# Kalibracija3.net
KiCad netlist of a schematic drawn in Altium Designer
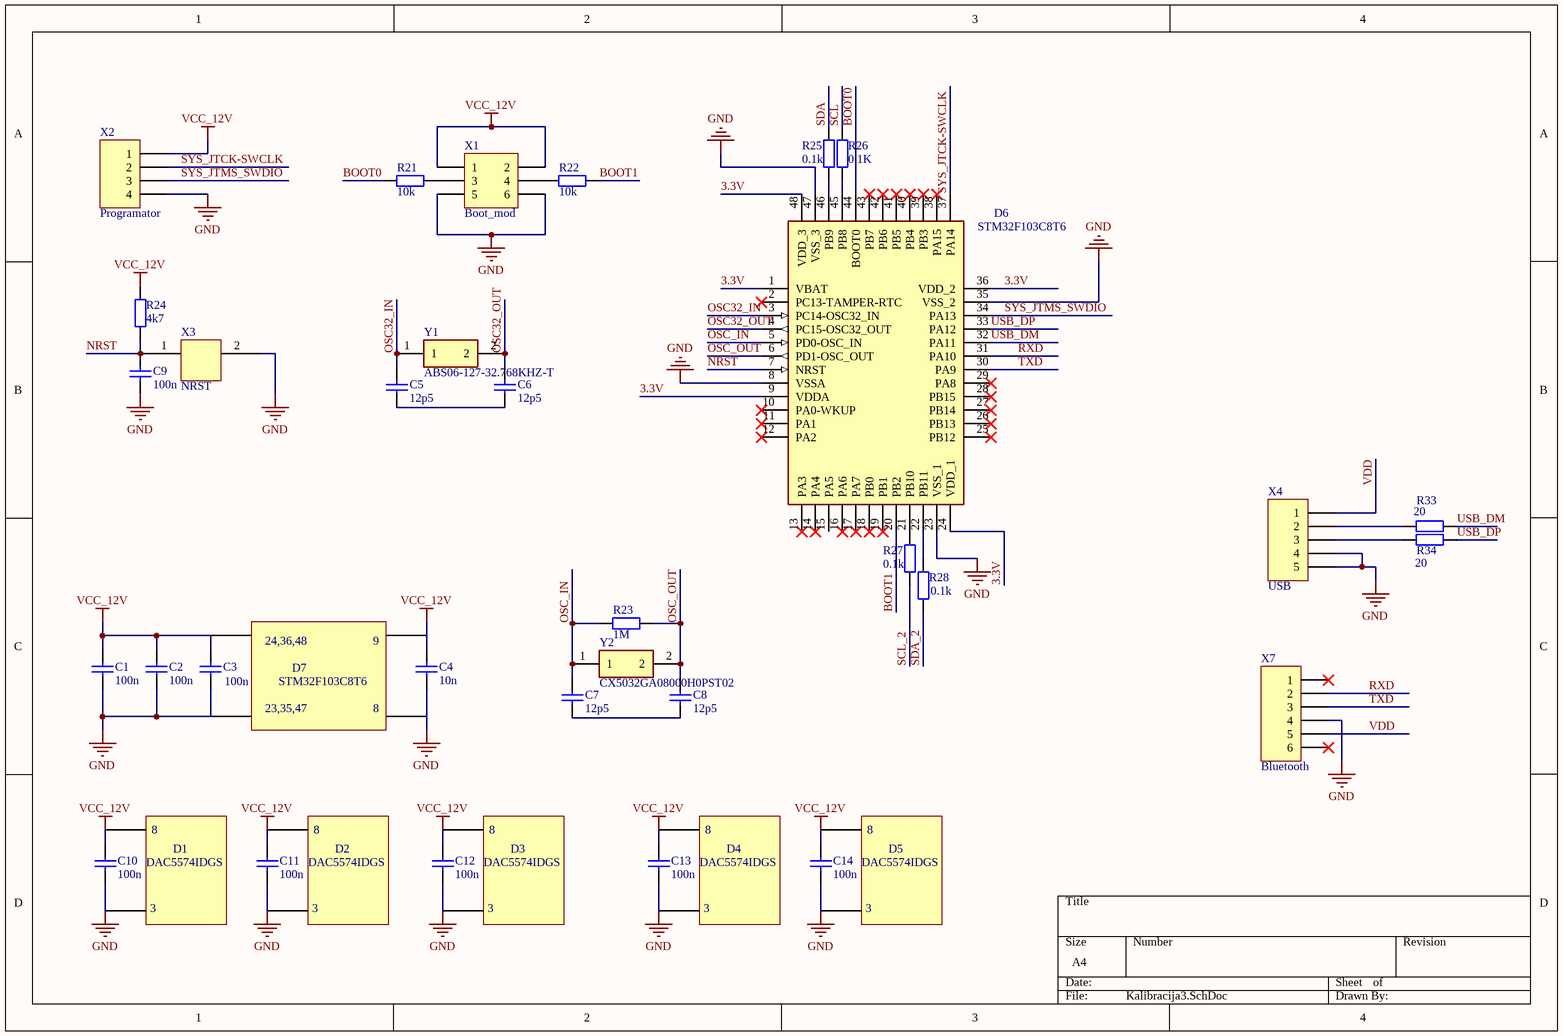
[diagram p0: Kalibracija3.SchDoc]

(export (version "E")
  (design (tool "Eeschema 10.0.6"))
  (components
    (comp (ref "C1")
      (value "100n")
      (footprint "6-0805_N")
      (description "Capacitor")
      (fields (field (name "PUBLISHER") "Altium Limited"))
      (libsource (lib "Miscellaneous Devices") (part "Cap"))
    )
    (comp (ref "C2")
      (value "100n")
      (footprint "6-0805_N")
      (description "Capacitor")
      (fields (field (name "PUBLISHER") "Altium Limited"))
      (libsource (lib "Miscellaneous Devices") (part "Cap"))
    )
    (comp (ref "C3")
      (value "100n")
      (footprint "6-0805_N")
      (description "Capacitor")
      (fields (field (name "PUBLISHER") "Altium Limited"))
      (libsource (lib "Miscellaneous Devices") (part "Cap"))
    )
    (comp (ref "C4")
      (value "10n")
      (footprint "6-0805_N")
      (description "Capacitor")
      (fields (field (name "PUBLISHER") "Altium Limited"))
      (libsource (lib "Miscellaneous Devices") (part "Cap"))
    )
    (comp (ref "C5")
      (value "12p5")
      (footprint "6-0805_N")
      (description "Capacitor")
      (fields (field (name "PUBLISHER") "Altium Limited"))
      (libsource (lib "Miscellaneous Devices") (part "Cap"))
    )
    (comp (ref "C6")
      (value "12p5")
      (footprint "6-0805_N")
      (description "Capacitor")
      (fields (field (name "PUBLISHER") "Altium Limited"))
      (libsource (lib "Miscellaneous Devices") (part "Cap"))
    )
    (comp (ref "C7")
      (value "12p5")
      (footprint "6-0805_N")
      (description "Capacitor")
      (fields (field (name "PUBLISHER") "Altium Limited"))
      (libsource (lib "Miscellaneous Devices") (part "Cap"))
    )
    (comp (ref "C8")
      (value "12p5")
      (footprint "6-0805_N")
      (description "Capacitor")
      (fields (field (name "PUBLISHER") "Altium Limited"))
      (libsource (lib "Miscellaneous Devices") (part "Cap"))
    )
    (comp (ref "C9")
      (value "100n")
      (footprint "6-0805_N")
      (description "Capacitor")
      (fields (field (name "PUBLISHER") "Altium Limited"))
      (libsource (lib "Miscellaneous Devices") (part "Cap"))
    )
    (comp (ref "C10")
      (value "100n")
      (footprint "6-0805_N")
      (description "Capacitor")
      (fields (field (name "PUBLISHER") "Altium Limited"))
      (libsource (lib "Miscellaneous Devices") (part "Cap"))
    )
    (comp (ref "C11")
      (value "100n")
      (footprint "6-0805_N")
      (description "Capacitor")
      (fields (field (name "PUBLISHER") "Altium Limited"))
      (libsource (lib "Miscellaneous Devices") (part "Cap"))
    )
    (comp (ref "C12")
      (value "100n")
      (footprint "6-0805_N")
      (description "Capacitor")
      (fields (field (name "PUBLISHER") "Altium Limited"))
      (libsource (lib "Miscellaneous Devices") (part "Cap"))
    )
    (comp (ref "C13")
      (value "100n")
      (footprint "6-0805_N")
      (description "Capacitor")
      (fields (field (name "PUBLISHER") "Altium Limited"))
      (libsource (lib "Miscellaneous Devices") (part "Cap"))
    )
    (comp (ref "C14")
      (value "100n")
      (footprint "6-0805_N")
      (description "Capacitor")
      (fields (field (name "PUBLISHER") "Altium Limited"))
      (libsource (lib "Miscellaneous Devices") (part "Cap"))
    )
    (comp (ref "D6")
      (value "STM32F103C8T6")
      (footprint "SamacSys:QFP50P900X900X160-48N")
      (description "Integrated Circuit")
      (fields
        (field (name "MOUSER PART NUMBER") "511-STM32F103C8T6")
        (field (name "RS PART NUMBER") "0402279P")
      )
      (libsource (lib "*") (part "STM32F103C8T6"))
    )
    (comp (ref "R21")
      (value "10k")
      (footprint "6-0805_N")
      (description "Resistor")
      (fields (field (name "PUBLISHER") "Altium Limited"))
      (libsource (lib "Miscellaneous Devices") (part "Res2"))
    )
    (comp (ref "R22")
      (value "10k")
      (footprint "6-0805_N")
      (description "Resistor")
      (fields (field (name "PUBLISHER") "Altium Limited"))
      (libsource (lib "Miscellaneous Devices") (part "Res2"))
    )
    (comp (ref "R23")
      (value "1M")
      (footprint "6-0805_N")
      (description "Resistor")
      (fields (field (name "PUBLISHER") "Altium Limited"))
      (libsource (lib "") (part "Res2_1"))
    )
    (comp (ref "R24")
      (value "4k7")
      (footprint "6-0805_N")
      (description "Resistor")
      (fields (field (name "PUBLISHER") "Altium Limited"))
      (libsource (lib "") (part "Res2_3"))
    )
    (comp (ref "R25")
      (value "0.1k")
      (footprint "6-0805_N")
      (description "Resistor")
      (fields (field (name "PUBLISHER") "Altium Limited"))
      (libsource (lib "") (part "Res2_2"))
    )
    (comp (ref "R26")
      (value "0.1K")
      (footprint "6-0805_N")
      (description "Resistor")
      (fields (field (name "PUBLISHER") "Altium Limited"))
      (libsource (lib "") (part "Res2_2"))
    )
    (comp (ref "R27")
      (value "0.1k")
      (footprint "6-0805_N")
      (description "Resistor")
      (fields (field (name "PUBLISHER") "Altium Limited"))
      (libsource (lib "") (part "Res2_2"))
    )
    (comp (ref "R28")
      (value "0.1k")
      (footprint "AXIAL-0.4")
      (description "Resistor")
      (fields (field (name "Comment") "Res2") (field (name "PUBLISHER") "Altium Limited"))
      (libsource (lib "") (part "Res2_2"))
    )
    (comp (ref "R33")
      (value "20")
      (footprint "6-0805_N")
      (description "Resistor")
      (fields (field (name "PUBLISHER") "Altium Limited"))
      (libsource (lib "") (part "Res2_1"))
    )
    (comp (ref "R34")
      (value "20")
      (footprint "6-0805_N")
      (description "Resistor")
      (fields (field (name "PUBLISHER") "Altium Limited"))
      (libsource (lib "") (part "Res2_1"))
    )
    (comp (ref "X1")
      (value "Boot_mod")
      (footprint "HDR2X3")
      (description "Header, 3-Pin, Dual row")
      (fields (field (name "PUBLISHER") "Altium Limited"))
      (libsource (lib "Miscellaneous Connectors") (part "Header 3X2"))
    )
    (comp (ref "X2")
      (value "Programator")
      (footprint "HDR1X4")
      (description "Header, 4-Pin")
      (fields (field (name "PUBLISHER") "Altium Limited"))
      (libsource (lib "Miscellaneous Connectors") (part "Header 4"))
    )
    (comp (ref "X3")
      (value "NRST")
      (footprint "HDR1X2")
      (libsource (lib "altium-import") (part "root_1_jumper_"))
    )
    (comp (ref "X4")
      (value "USB")
      (footprint "HDR1X5")
      (description "Header, 5-Pin")
      (fields (field (name "PUBLISHER") "Altium Limited"))
      (libsource (lib "Miscellaneous Connectors") (part "Header 5"))
    )
    (comp (ref "X7")
      (value "Bluetooth")
      (footprint "HDR1X6")
      (description "Header, 6-Pin")
      (fields (field (name "PUBLISHER") "Altium Limited"))
      (libsource (lib "Miscellaneous Connectors") (part "Header 6"))
    )
    (comp (ref "Y1")
      (value "ABS06-127-32.768KHZ-T")
      (footprint "SamacSys:ABS0612732768KHZT")
      (description "Crystal or Oscillator")
      (fields
        (field (name "MOUSER PART NUMBER") "815-ABS0612732.768KT")
        (field (name "RS PART NUMBER") "1753472P")
      )
      (libsource (lib "*") (part "ABS06-127-32.768KHZ-T"))
    )
    (comp (ref "Y2")
      (value "CX5032GA08000H0PST02")
      (footprint "SamacSys:CX5032GA08000H0PST02")
      (description "Crystal or Oscillator")
      (fields (field (name "MOUSER PART NUMBER") "581-CX5032GA08H0PST"))
      (libsource (lib "*") (part "CX5032GA08000H0PST02"))
    )
  )
  (nets
    (net (code "1") (name "/3.3V") (class "Default")
      (node (ref "D6") (pin "1") (pinfunction "VBAT_1") (pintype "passive"))
      (node (ref "D6") (pin "24") (pinfunction "VDD_1_24") (pintype "power_in"))
      (node (ref "D6") (pin "36") (pinfunction "VDD_2_36") (pintype "power_in"))
      (node (ref "D6") (pin "48") (pinfunction "VDD_3_48") (pintype "power_in"))
      (node (ref "D6") (pin "9") (pinfunction "VDDA_9") (pintype "power_in"))
    )
    (net (code "2") (name "/BOOT0") (class "Default")
      (node (ref "D6") (pin "44") (pinfunction "BOOT0_44") (pintype "passive"))
      (node (ref "R21") (pin "2") (pinfunction "2_2") (pintype "passive"))
    )
    (net (code "3") (name "/BOOT1") (class "Default")
      (node (ref "D6") (pin "20") (pinfunction "PB2_20") (pintype "passive"))
      (node (ref "R22") (pin "1") (pinfunction "1_1") (pintype "passive"))
    )
    (net (code "4") (name "/NRST") (class "Default")
      (node (ref "C9") (pin "2") (pinfunction "2_2") (pintype "passive"))
      (node (ref "D6") (pin "7") (pinfunction "NRST_7") (pintype "input"))
      (node (ref "R24") (pin "2") (pinfunction "2_2") (pintype "passive"))
      (node (ref "X3") (pin "1") (pintype "passive"))
    )
    (net (code "5") (name "/OSC32_IN") (class "Default")
      (node (ref "C5") (pin "2") (pinfunction "2_2") (pintype "passive"))
      (node (ref "D6") (pin "3") (pinfunction "PC14-OSC32_IN_3") (pintype "input"))
      (node (ref "Y1") (pin "1") (pinfunction "1_1") (pintype "passive"))
    )
    (net (code "6") (name "/OSC32_OUT") (class "Default")
      (node (ref "C6") (pin "2") (pinfunction "2_2") (pintype "passive"))
      (node (ref "D6") (pin "4") (pinfunction "PC15-OSC32_OUT_4") (pintype "output"))
      (node (ref "Y1") (pin "2") (pinfunction "2_2") (pintype "passive"))
    )
    (net (code "7") (name "/OSC_IN") (class "Default")
      (node (ref "C7") (pin "2") (pinfunction "2_2") (pintype "passive"))
      (node (ref "D6") (pin "5") (pinfunction "PD0-OSC_IN_5") (pintype "input"))
      (node (ref "R23") (pin "1") (pinfunction "1_1") (pintype "passive"))
      (node (ref "Y2") (pin "1") (pinfunction "1_1") (pintype "passive"))
    )
    (net (code "8") (name "/OSC_OUT") (class "Default")
      (node (ref "C8") (pin "2") (pinfunction "2_2") (pintype "passive"))
      (node (ref "D6") (pin "6") (pinfunction "PD1-OSC_OUT_6") (pintype "output"))
      (node (ref "R23") (pin "2") (pinfunction "2_2") (pintype "passive"))
      (node (ref "Y2") (pin "2") (pinfunction "2_2") (pintype "passive"))
    )
    (net (code "9") (name "/RXD") (class "Default")
      (node (ref "D6") (pin "31") (pinfunction "PA10_31") (pintype "passive"))
      (node (ref "X7") (pin "2") (pinfunction "2_2") (pintype "passive"))
    )
    (net (code "10") (name "/SCL") (class "Default")
      (node (ref "R26") (pin "2") (pinfunction "2_2") (pintype "passive"))
    )
    (net (code "11") (name "/SCL_2") (class "Default")
      (node (ref "R27") (pin "1") (pinfunction "1_1") (pintype "passive"))
    )
    (net (code "12") (name "/SDA") (class "Default")
      (node (ref "R25") (pin "2") (pinfunction "2_2") (pintype "passive"))
    )
    (net (code "13") (name "/SDA_2") (class "Default")
      (node (ref "R28") (pin "1") (pinfunction "1_1") (pintype "passive"))
    )
    (net (code "14") (name "/SYS_JTCK-SWCLK") (class "Default")
      (node (ref "D6") (pin "37") (pinfunction "PA14_37") (pintype "passive"))
      (node (ref "X2") (pin "2") (pinfunction "2_2") (pintype "passive"))
    )
    (net (code "15") (name "/SYS_JTMS_SWDIO") (class "Default")
      (node (ref "D6") (pin "34") (pinfunction "PA13_34") (pintype "passive"))
      (node (ref "X2") (pin "3") (pinfunction "3_3") (pintype "passive"))
    )
    (net (code "16") (name "/TXD") (class "Default")
      (node (ref "D6") (pin "30") (pinfunction "PA9_30") (pintype "passive"))
      (node (ref "X7") (pin "3") (pinfunction "3_3") (pintype "passive"))
    )
    (net (code "17") (name "/USB_DM") (class "Default")
      (node (ref "D6") (pin "32") (pinfunction "PA11_32") (pintype "passive"))
      (node (ref "R33") (pin "2") (pinfunction "2_2") (pintype "passive"))
    )
    (net (code "18") (name "/USB_DP") (class "Default")
      (node (ref "D6") (pin "33") (pinfunction "PA12_33") (pintype "passive"))
      (node (ref "R34") (pin "2") (pinfunction "2_2") (pintype "passive"))
    )
    (net (code "19") (name "/VDD") (class "Default")
      (node (ref "X4") (pin "1") (pinfunction "1_1") (pintype "passive"))
      (node (ref "X7") (pin "5") (pinfunction "5_5") (pintype "passive"))
    )
    (net (code "20") (name "GND") (class "Default")
      (node (ref "C1") (pin "1") (pinfunction "1_1") (pintype "passive"))
      (node (ref "C10") (pin "1") (pinfunction "1_1") (pintype "passive"))
      (node (ref "C11") (pin "1") (pinfunction "1_1") (pintype "passive"))
      (node (ref "C12") (pin "1") (pinfunction "1_1") (pintype "passive"))
      (node (ref "C13") (pin "1") (pinfunction "1_1") (pintype "passive"))
      (node (ref "C14") (pin "1") (pinfunction "1_1") (pintype "passive"))
      (node (ref "C2") (pin "1") (pinfunction "1_1") (pintype "passive"))
      (node (ref "C3") (pin "1") (pinfunction "1_1") (pintype "passive"))
      (node (ref "C4") (pin "1") (pinfunction "1_1") (pintype "passive"))
      (node (ref "C9") (pin "1") (pinfunction "1_1") (pintype "passive"))
      (node (ref "D6") (pin "23") (pinfunction "VSS_1_23") (pintype "power_in"))
      (node (ref "D6") (pin "35") (pinfunction "VSS_2_35") (pintype "power_in"))
      (node (ref "D6") (pin "47") (pinfunction "VSS_3_47") (pintype "power_in"))
      (node (ref "D6") (pin "8") (pinfunction "VSSA_8") (pintype "power_in"))
      (node (ref "X1") (pin "5") (pinfunction "5_5") (pintype "passive"))
      (node (ref "X1") (pin "6") (pinfunction "6_6") (pintype "passive"))
      (node (ref "X2") (pin "4") (pinfunction "4_4") (pintype "passive"))
      (node (ref "X3") (pin "2") (pinfunction "10_2") (pintype "power_in"))
      (node (ref "X4") (pin "4") (pinfunction "4_4") (pintype "passive"))
      (node (ref "X4") (pin "5") (pinfunction "5_5") (pintype "passive"))
      (node (ref "X7") (pin "4") (pinfunction "4_4") (pintype "passive"))
    )
    (net (code "21") (name "Net-(C5-Pad1)") (class "Default")
      (node (ref "C5") (pin "1") (pinfunction "1_1") (pintype "passive"))
      (node (ref "C6") (pin "1") (pinfunction "1_1") (pintype "passive"))
    )
    (net (code "22") (name "Net-(C7-Pad1)") (class "Default")
      (node (ref "C7") (pin "1") (pinfunction "1_1") (pintype "passive"))
      (node (ref "C8") (pin "1") (pinfunction "1_1") (pintype "passive"))
    )
    (net (code "23") (name "Net-(D6-PB8)") (class "Default")
      (node (ref "D6") (pin "45") (pinfunction "PB8_45") (pintype "passive"))
      (node (ref "R26") (pin "1") (pinfunction "1_1") (pintype "passive"))
    )
    (net (code "24") (name "Net-(D6-PB9)") (class "Default")
      (node (ref "D6") (pin "46") (pinfunction "PB9_46") (pintype "passive"))
      (node (ref "R25") (pin "1") (pinfunction "1_1") (pintype "passive"))
    )
    (net (code "25") (name "Net-(D6-PB10)") (class "Default")
      (node (ref "D6") (pin "21") (pinfunction "PB10_21") (pintype "passive"))
      (node (ref "R27") (pin "2") (pinfunction "2_2") (pintype "passive"))
    )
    (net (code "26") (name "Net-(D6-PB11)") (class "Default")
      (node (ref "D6") (pin "22") (pinfunction "PB11_22") (pintype "passive"))
      (node (ref "R28") (pin "2") (pinfunction "2_2") (pintype "passive"))
    )
    (net (code "27") (name "Net-(R21-Pad1)") (class "Default")
      (node (ref "R21") (pin "1") (pinfunction "1_1") (pintype "passive"))
      (node (ref "X1") (pin "3") (pinfunction "3_3") (pintype "passive"))
    )
    (net (code "28") (name "Net-(R22-Pad2)") (class "Default")
      (node (ref "R22") (pin "2") (pinfunction "2_2") (pintype "passive"))
      (node (ref "X1") (pin "4") (pinfunction "4_4") (pintype "passive"))
    )
    (net (code "29") (name "Net-(R33-Pad1)") (class "Default")
      (node (ref "R33") (pin "1") (pinfunction "1_1") (pintype "passive"))
      (node (ref "X4") (pin "2") (pinfunction "2_2") (pintype "passive"))
    )
    (net (code "30") (name "Net-(R34-Pad1)") (class "Default")
      (node (ref "R34") (pin "1") (pinfunction "1_1") (pintype "passive"))
      (node (ref "X4") (pin "3") (pinfunction "3_3") (pintype "passive"))
    )
    (net (code "31") (name "VCC_12V") (class "Default")
      (node (ref "C1") (pin "2") (pinfunction "2_2") (pintype "passive"))
      (node (ref "C10") (pin "2") (pinfunction "2_2") (pintype "passive"))
      (node (ref "C11") (pin "2") (pinfunction "2_2") (pintype "passive"))
      (node (ref "C12") (pin "2") (pinfunction "2_2") (pintype "passive"))
      (node (ref "C13") (pin "2") (pinfunction "2_2") (pintype "passive"))
      (node (ref "C14") (pin "2") (pinfunction "2_2") (pintype "passive"))
      (node (ref "C2") (pin "2") (pinfunction "2_2") (pintype "passive"))
      (node (ref "C3") (pin "2") (pinfunction "2_2") (pintype "passive"))
      (node (ref "C4") (pin "2") (pinfunction "2_2") (pintype "passive"))
      (node (ref "R24") (pin "1") (pinfunction "1_1") (pintype "passive"))
      (node (ref "X1") (pin "1") (pinfunction "1_1") (pintype "passive"))
      (node (ref "X1") (pin "2") (pinfunction "2_2") (pintype "passive"))
      (node (ref "X2") (pin "1") (pinfunction "1_1") (pintype "passive"))
    )
    (net (code "32") (name "unconnected-(D6-PA0-WKUP-Pad10)") (class "Default")
      (node (ref "D6") (pin "10") (pinfunction "PA0-WKUP_10") (pintype "passive+no_connect"))
    )
    (net (code "33") (name "unconnected-(D6-PA1-Pad11)") (class "Default")
      (node (ref "D6") (pin "11") (pinfunction "PA1_11") (pintype "passive+no_connect"))
    )
    (net (code "34") (name "unconnected-(D6-PA2-Pad12)") (class "Default")
      (node (ref "D6") (pin "12") (pinfunction "PA2_12") (pintype "passive+no_connect"))
    )
    (net (code "35") (name "unconnected-(D6-PA3-Pad13)") (class "Default")
      (node (ref "D6") (pin "13") (pinfunction "PA3_13") (pintype "passive+no_connect"))
    )
    (net (code "36") (name "unconnected-(D6-PA4-Pad14)") (class "Default")
      (node (ref "D6") (pin "14") (pinfunction "PA4_14") (pintype "passive+no_connect"))
    )
    (net (code "37") (name "unconnected-(D6-PA5-Pad15)") (class "Default")
      (node (ref "D6") (pin "15") (pinfunction "PA5_15") (pintype "passive"))
    )
    (net (code "38") (name "unconnected-(D6-PA6-Pad16)") (class "Default")
      (node (ref "D6") (pin "16") (pinfunction "PA6_16") (pintype "passive+no_connect"))
    )
    (net (code "39") (name "unconnected-(D6-PA7-Pad17)") (class "Default")
      (node (ref "D6") (pin "17") (pinfunction "PA7_17") (pintype "passive+no_connect"))
    )
    (net (code "40") (name "unconnected-(D6-PA8-Pad29)") (class "Default")
      (node (ref "D6") (pin "29") (pinfunction "PA8_29") (pintype "passive+no_connect"))
    )
    (net (code "41") (name "unconnected-(D6-PA15-Pad38)") (class "Default")
      (node (ref "D6") (pin "38") (pinfunction "PA15_38") (pintype "passive+no_connect"))
    )
    (net (code "42") (name "unconnected-(D6-PB0-Pad18)") (class "Default")
      (node (ref "D6") (pin "18") (pinfunction "PB0_18") (pintype "passive+no_connect"))
    )
    (net (code "43") (name "unconnected-(D6-PB1-Pad19)") (class "Default")
      (node (ref "D6") (pin "19") (pinfunction "PB1_19") (pintype "passive+no_connect"))
    )
    (net (code "44") (name "unconnected-(D6-PB3-Pad39)") (class "Default")
      (node (ref "D6") (pin "39") (pinfunction "PB3_39") (pintype "passive+no_connect"))
    )
    (net (code "45") (name "unconnected-(D6-PB4-Pad40)") (class "Default")
      (node (ref "D6") (pin "40") (pinfunction "PB4_40") (pintype "passive+no_connect"))
    )
    (net (code "46") (name "unconnected-(D6-PB5-Pad41)") (class "Default")
      (node (ref "D6") (pin "41") (pinfunction "PB5_41") (pintype "passive+no_connect"))
    )
    (net (code "47") (name "unconnected-(D6-PB6-Pad42)") (class "Default")
      (node (ref "D6") (pin "42") (pinfunction "PB6_42") (pintype "passive+no_connect"))
    )
    (net (code "48") (name "unconnected-(D6-PB7-Pad43)") (class "Default")
      (node (ref "D6") (pin "43") (pinfunction "PB7_43") (pintype "passive+no_connect"))
    )
    (net (code "49") (name "unconnected-(D6-PB12-Pad25)") (class "Default")
      (node (ref "D6") (pin "25") (pinfunction "PB12_25") (pintype "passive+no_connect"))
    )
    (net (code "50") (name "unconnected-(D6-PB13-Pad26)") (class "Default")
      (node (ref "D6") (pin "26") (pinfunction "PB13_26") (pintype "passive+no_connect"))
    )
    (net (code "51") (name "unconnected-(D6-PB14-Pad27)") (class "Default")
      (node (ref "D6") (pin "27") (pinfunction "PB14_27") (pintype "passive+no_connect"))
    )
    (net (code "52") (name "unconnected-(D6-PB15-Pad28)") (class "Default")
      (node (ref "D6") (pin "28") (pinfunction "PB15_28") (pintype "passive+no_connect"))
    )
    (net (code "53") (name "unconnected-(D6-PC13-TAMPER-RTC-Pad2)") (class "Default")
      (node (ref "D6") (pin "2") (pinfunction "PC13-TAMPER-RTC_2") (pintype "passive+no_connect"))
    )
    (net (code "54") (name "unconnected-(X7-Pad1)") (class "Default")
      (node (ref "X7") (pin "1") (pinfunction "1_1") (pintype "passive+no_connect"))
    )
    (net (code "55") (name "unconnected-(X7-Pad6)") (class "Default")
      (node (ref "X7") (pin "6") (pinfunction "6_6") (pintype "passive+no_connect"))
    )
  )
)
